# DMD_Output_Interface.net
KiCad netlist of a schematic drawn in Altium Designer
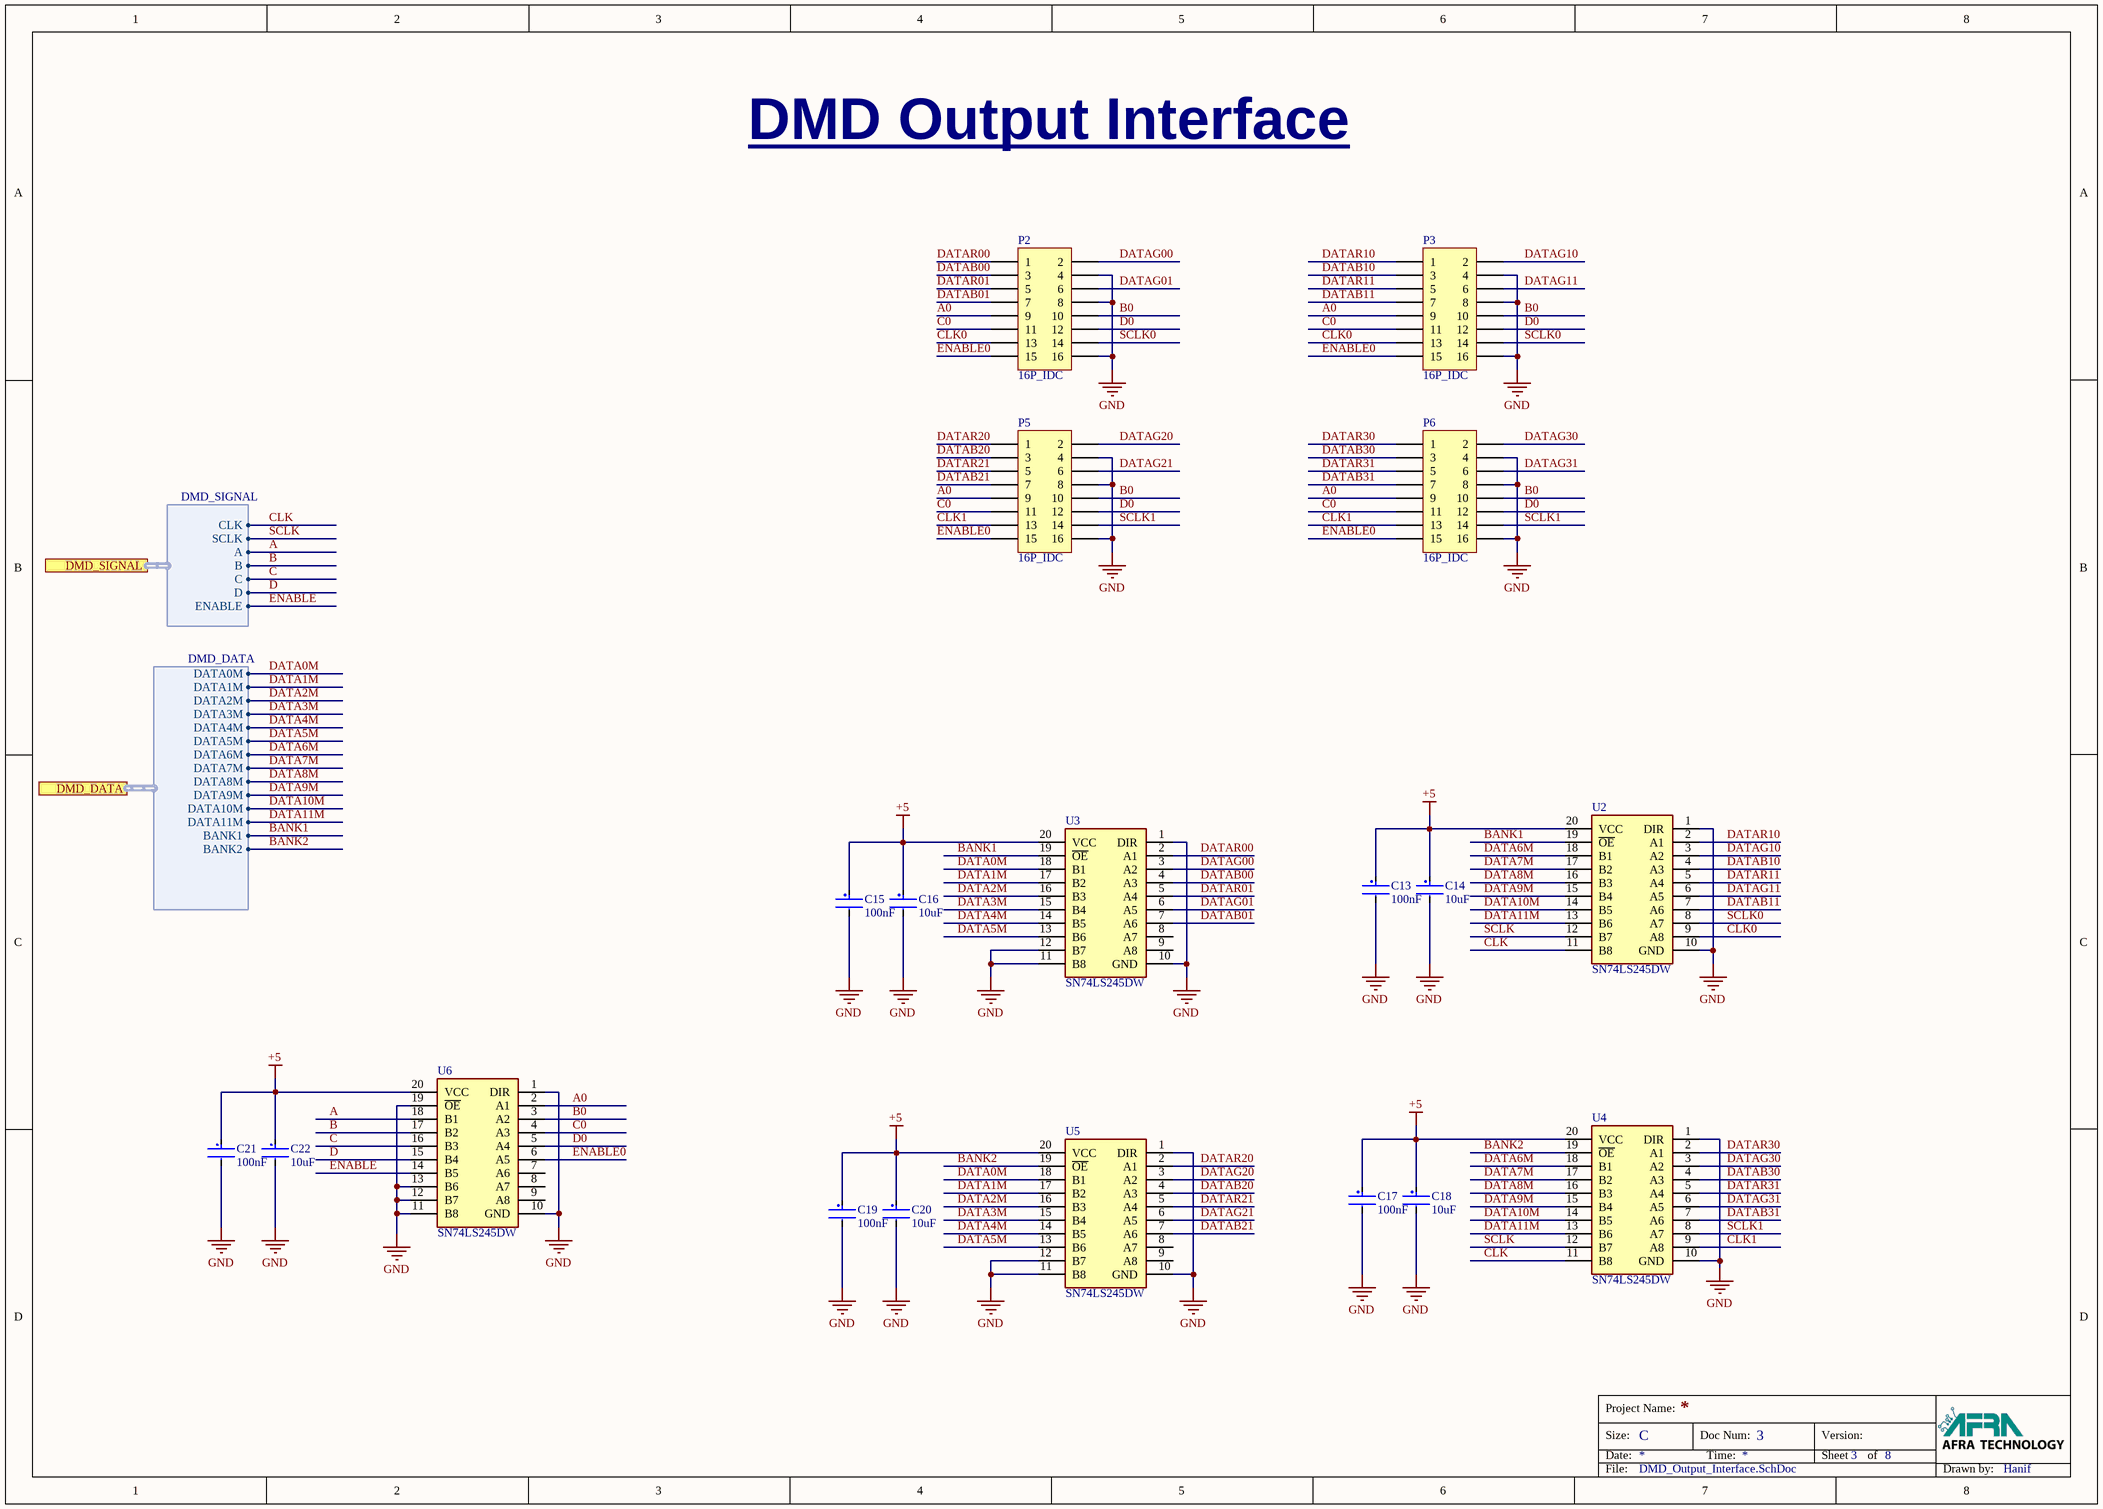
[diagram p0: DMD_Output_Interface.SchDoc]

(export (version "E")
  (design (tool "Eeschema 10.0.6"))
  (components
    (comp (ref "C13")
      (value "100nF")
      (footprint "Samsung_CL31_IPC_A_1206")
      (description "CAP CER 0.1UF 50V X7R 1206, ±10% 50V Ceramic Capacitor X7R 1206 (3216 Metric)")
      (libsource (lib "DMD_Card") (part "CL31B104KBCNFNC"))
    )
    (comp (ref "C14")
      (value "10uF")
      (footprint "Samsung_CL31_IPC_A_1206")
      (description "CAP CER 10UF 6.3V X5R 1206, ±10% 6.3V Ceramic Capacitor X5R 1206 (3216 Metric)")
      (libsource (lib "DMD_Card") (part "CL31A106KQHNNWE"))
    )
    (comp (ref "C15")
      (value "100nF")
      (footprint "Samsung_CL31_IPC_A_1206")
      (description "CAP CER 0.1UF 50V X7R 1206, ±10% 50V Ceramic Capacitor X7R 1206 (3216 Metric)")
      (libsource (lib "DMD_Card") (part "CL31B104KBCNFNC"))
    )
    (comp (ref "C16")
      (value "10uF")
      (footprint "Samsung_CL31_IPC_A_1206")
      (description "CAP CER 10UF 6.3V X5R 1206, ±10% 6.3V Ceramic Capacitor X5R 1206 (3216 Metric)")
      (libsource (lib "DMD_Card") (part "CL31A106KQHNNWE"))
    )
    (comp (ref "C17")
      (value "100nF")
      (footprint "Samsung_CL31_IPC_A_1206")
      (description "CAP CER 0.1UF 50V X7R 1206, ±10% 50V Ceramic Capacitor X7R 1206 (3216 Metric)")
      (libsource (lib "DMD_Card") (part "CL31B104KBCNFNC"))
    )
    (comp (ref "C18")
      (value "10uF")
      (footprint "Samsung_CL31_IPC_A_1206")
      (description "CAP CER 10UF 6.3V X5R 1206, ±10% 6.3V Ceramic Capacitor X5R 1206 (3216 Metric)")
      (libsource (lib "DMD_Card") (part "CL31A106KQHNNWE"))
    )
    (comp (ref "C19")
      (value "100nF")
      (footprint "Samsung_CL31_IPC_A_1206")
      (description "CAP CER 0.1UF 50V X7R 1206, ±10% 50V Ceramic Capacitor X7R 1206 (3216 Metric)")
      (libsource (lib "DMD_Card") (part "CL31B104KBCNFNC"))
    )
    (comp (ref "C20")
      (value "10uF")
      (footprint "Samsung_CL31_IPC_A_1206")
      (description "CAP CER 10UF 6.3V X5R 1206, ±10% 6.3V Ceramic Capacitor X5R 1206 (3216 Metric)")
      (libsource (lib "DMD_Card") (part "CL31A106KQHNNWE"))
    )
    (comp (ref "C21")
      (value "100nF")
      (footprint "Samsung_CL31_IPC_A_1206")
      (description "CAP CER 0.1UF 50V X7R 1206, ±10% 50V Ceramic Capacitor X7R 1206 (3216 Metric)")
      (libsource (lib "DMD_Card") (part "CL31B104KBCNFNC"))
    )
    (comp (ref "C22")
      (value "10uF")
      (footprint "Samsung_CL31_IPC_A_1206")
      (description "CAP CER 10UF 6.3V X5R 1206, ±10% 6.3V Ceramic Capacitor X5R 1206 (3216 Metric)")
      (libsource (lib "DMD_Card") (part "CL31A106KQHNNWE"))
    )
    (comp (ref "P2")
      (value "16P_IDC")
      (footprint "16Pin_IDC_Connector")
      (description "Headers & Wire Housings 16P STRAIGHT")
      (fields
        (field (name "MANUFACTURER") "Adam Equipment")
        (field (name "MANUFACTURER PART NUMBER") "BHR-16-VUA")
      )
      (libsource (lib "DMD_Card") (part "BHR-16-VUA"))
    )
    (comp (ref "P3")
      (value "16P_IDC")
      (footprint "16Pin_IDC_Connector")
      (description "Headers & Wire Housings 16P STRAIGHT")
      (fields
        (field (name "MANUFACTURER") "Adam Equipment")
        (field (name "MANUFACTURER PART NUMBER") "BHR-16-VUA")
      )
      (libsource (lib "DMD_Card") (part "BHR-16-VUA"))
    )
    (comp (ref "P5")
      (value "16P_IDC")
      (footprint "16Pin_IDC_Connector")
      (description "Headers & Wire Housings 16P STRAIGHT")
      (fields
        (field (name "MANUFACTURER") "Adam Equipment")
        (field (name "MANUFACTURER PART NUMBER") "BHR-16-VUA")
      )
      (libsource (lib "DMD_Card") (part "BHR-16-VUA"))
    )
    (comp (ref "P6")
      (value "16P_IDC")
      (footprint "16Pin_IDC_Connector")
      (description "Headers & Wire Housings 16P STRAIGHT")
      (fields
        (field (name "MANUFACTURER") "Adam Equipment")
        (field (name "MANUFACTURER PART NUMBER") "BHR-16-VUA")
      )
      (libsource (lib "DMD_Card") (part "BHR-16-VUA"))
    )
    (comp (ref "U2")
      (value "SN74LS245DW")
      (footprint "SOIC127P1030X265-20N")
      (description "Integrated Circuit")
      (fields (field (name "MOUSER PART NUMBER") "595-SN74LS245DW"))
      (libsource (lib "DMD_Controller_Card") (part "SN74LS245DW"))
    )
    (comp (ref "U3")
      (value "SN74LS245DW")
      (footprint "SOIC127P1030X265-20N")
      (description "Integrated Circuit")
      (fields (field (name "MOUSER PART NUMBER") "595-SN74LS245DW"))
      (libsource (lib "DMD_Controller_Card") (part "SN74LS245DW"))
    )
    (comp (ref "U4")
      (value "SN74LS245DW")
      (footprint "SOIC127P1030X265-20N")
      (description "Integrated Circuit")
      (fields (field (name "MOUSER PART NUMBER") "595-SN74LS245DW"))
      (libsource (lib "DMD_Controller_Card") (part "SN74LS245DW"))
    )
    (comp (ref "U5")
      (value "SN74LS245DW")
      (footprint "SOIC127P1030X265-20N")
      (description "Integrated Circuit")
      (fields (field (name "MOUSER PART NUMBER") "595-SN74LS245DW"))
      (libsource (lib "DMD_Controller_Card") (part "SN74LS245DW"))
    )
    (comp (ref "U6")
      (value "SN74LS245DW")
      (footprint "SOIC127P1030X265-20N")
      (description "Integrated Circuit")
      (fields (field (name "MOUSER PART NUMBER") "595-SN74LS245DW"))
      (libsource (lib "DMD_Controller_Card") (part "SN74LS245DW"))
    )
  )
  (nets
    (net (code "3") (name "+5") (class "Default")
      (node (ref "C13") (pin "1") (pinfunction "1_1") (pintype "passive"))
      (node (ref "C14") (pin "1") (pinfunction "1_1") (pintype "passive"))
      (node (ref "C15") (pin "1") (pinfunction "1_1") (pintype "passive"))
      (node (ref "C16") (pin "1") (pinfunction "1_1") (pintype "passive"))
      (node (ref "C17") (pin "1") (pinfunction "1_1") (pintype "passive"))
      (node (ref "C18") (pin "1") (pinfunction "1_1") (pintype "passive"))
      (node (ref "C19") (pin "1") (pinfunction "1_1") (pintype "passive"))
      (node (ref "C20") (pin "1") (pinfunction "1_1") (pintype "passive"))
      (node (ref "C21") (pin "1") (pinfunction "1_1") (pintype "passive"))
      (node (ref "C22") (pin "1") (pinfunction "1_1") (pintype "passive"))
      (node (ref "U2") (pin "20") (pinfunction "VCC_20") (pintype "passive"))
      (node (ref "U3") (pin "20") (pinfunction "VCC_20") (pintype "passive"))
      (node (ref "U4") (pin "20") (pinfunction "VCC_20") (pintype "passive"))
      (node (ref "U5") (pin "20") (pinfunction "VCC_20") (pintype "passive"))
      (node (ref "U6") (pin "20") (pinfunction "VCC_20") (pintype "passive"))
    )
    (net (code "4") (name "/A") (class "Default")
      (node (ref "U6") (pin "18") (pinfunction "B1_18") (pintype "passive"))
    )
    (net (code "5") (name "/A0") (class "Default")
      (node (ref "P2") (pin "9") (pinfunction "9_9") (pintype "passive"))
      (node (ref "P3") (pin "9") (pinfunction "9_9") (pintype "passive"))
      (node (ref "P5") (pin "9") (pinfunction "9_9") (pintype "passive"))
      (node (ref "P6") (pin "9") (pinfunction "9_9") (pintype "passive"))
      (node (ref "U6") (pin "2") (pinfunction "A1_2") (pintype "passive"))
    )
    (net (code "6") (name "/B") (class "Default")
      (node (ref "U6") (pin "17") (pinfunction "B2_17") (pintype "passive"))
    )
    (net (code "7") (name "/B0") (class "Default")
      (node (ref "P2") (pin "10") (pinfunction "10_10") (pintype "passive"))
      (node (ref "P3") (pin "10") (pinfunction "10_10") (pintype "passive"))
      (node (ref "P5") (pin "10") (pinfunction "10_10") (pintype "passive"))
      (node (ref "P6") (pin "10") (pinfunction "10_10") (pintype "passive"))
      (node (ref "U6") (pin "3") (pinfunction "A2_3") (pintype "passive"))
    )
    (net (code "8") (name "/BANK1") (class "Default")
      (node (ref "U2") (pin "19") (pinfunction "~{OE}_19") (pintype "passive"))
      (node (ref "U3") (pin "19") (pinfunction "~{OE}_19") (pintype "passive"))
    )
    (net (code "9") (name "/BANK2") (class "Default")
      (node (ref "U4") (pin "19") (pinfunction "~{OE}_19") (pintype "passive"))
      (node (ref "U5") (pin "19") (pinfunction "~{OE}_19") (pintype "passive"))
    )
    (net (code "10") (name "/C") (class "Default")
      (node (ref "U6") (pin "16") (pinfunction "B3_16") (pintype "passive"))
    )
    (net (code "11") (name "/C0") (class "Default")
      (node (ref "P2") (pin "11") (pinfunction "11_11") (pintype "passive"))
      (node (ref "P3") (pin "11") (pinfunction "11_11") (pintype "passive"))
      (node (ref "P5") (pin "11") (pinfunction "11_11") (pintype "passive"))
      (node (ref "P6") (pin "11") (pinfunction "11_11") (pintype "passive"))
      (node (ref "U6") (pin "4") (pinfunction "A3_4") (pintype "passive"))
    )
    (net (code "12") (name "/CLK") (class "Default")
      (node (ref "U2") (pin "11") (pinfunction "B8_11") (pintype "passive"))
      (node (ref "U4") (pin "11") (pinfunction "B8_11") (pintype "passive"))
    )
    (net (code "13") (name "/CLK0") (class "Default")
      (node (ref "P2") (pin "13") (pinfunction "13_13") (pintype "passive"))
      (node (ref "P3") (pin "13") (pinfunction "13_13") (pintype "passive"))
      (node (ref "U2") (pin "9") (pinfunction "A8_9") (pintype "passive"))
    )
    (net (code "14") (name "/CLK1") (class "Default")
      (node (ref "P5") (pin "13") (pinfunction "13_13") (pintype "passive"))
      (node (ref "P6") (pin "13") (pinfunction "13_13") (pintype "passive"))
      (node (ref "U4") (pin "9") (pinfunction "A8_9") (pintype "passive"))
    )
    (net (code "15") (name "/D") (class "Default")
      (node (ref "U6") (pin "15") (pinfunction "B4_15") (pintype "passive"))
    )
    (net (code "16") (name "/D0") (class "Default")
      (node (ref "P2") (pin "12") (pinfunction "12_12") (pintype "passive"))
      (node (ref "P3") (pin "12") (pinfunction "12_12") (pintype "passive"))
      (node (ref "P5") (pin "12") (pinfunction "12_12") (pintype "passive"))
      (node (ref "P6") (pin "12") (pinfunction "12_12") (pintype "passive"))
      (node (ref "U6") (pin "5") (pinfunction "A4_5") (pintype "passive"))
    )
    (net (code "17") (name "/DATA0M") (class "Default")
      (node (ref "U3") (pin "18") (pinfunction "B1_18") (pintype "passive"))
      (node (ref "U5") (pin "18") (pinfunction "B1_18") (pintype "passive"))
    )
    (net (code "18") (name "/DATA1M") (class "Default")
      (node (ref "U3") (pin "17") (pinfunction "B2_17") (pintype "passive"))
      (node (ref "U5") (pin "17") (pinfunction "B2_17") (pintype "passive"))
    )
    (net (code "19") (name "/DATA2M") (class "Default")
      (node (ref "U3") (pin "16") (pinfunction "B3_16") (pintype "passive"))
      (node (ref "U5") (pin "16") (pinfunction "B3_16") (pintype "passive"))
    )
    (net (code "20") (name "/DATA3M") (class "Default")
      (node (ref "U3") (pin "15") (pinfunction "B4_15") (pintype "passive"))
      (node (ref "U5") (pin "15") (pinfunction "B4_15") (pintype "passive"))
    )
    (net (code "21") (name "/DATA4M") (class "Default")
      (node (ref "U3") (pin "14") (pinfunction "B5_14") (pintype "passive"))
      (node (ref "U5") (pin "14") (pinfunction "B5_14") (pintype "passive"))
    )
    (net (code "22") (name "/DATA5M") (class "Default")
      (node (ref "U3") (pin "13") (pinfunction "B6_13") (pintype "passive"))
      (node (ref "U5") (pin "13") (pinfunction "B6_13") (pintype "passive"))
    )
    (net (code "23") (name "/DATA6M") (class "Default")
      (node (ref "U2") (pin "18") (pinfunction "B1_18") (pintype "passive"))
      (node (ref "U4") (pin "18") (pinfunction "B1_18") (pintype "passive"))
    )
    (net (code "24") (name "/DATA7M") (class "Default")
      (node (ref "U2") (pin "17") (pinfunction "B2_17") (pintype "passive"))
      (node (ref "U4") (pin "17") (pinfunction "B2_17") (pintype "passive"))
    )
    (net (code "25") (name "/DATA8M") (class "Default")
      (node (ref "U2") (pin "16") (pinfunction "B3_16") (pintype "passive"))
      (node (ref "U4") (pin "16") (pinfunction "B3_16") (pintype "passive"))
    )
    (net (code "26") (name "/DATA9M") (class "Default")
      (node (ref "U2") (pin "15") (pinfunction "B4_15") (pintype "passive"))
      (node (ref "U4") (pin "15") (pinfunction "B4_15") (pintype "passive"))
    )
    (net (code "27") (name "/DATA10M") (class "Default")
      (node (ref "U2") (pin "14") (pinfunction "B5_14") (pintype "passive"))
      (node (ref "U4") (pin "14") (pinfunction "B5_14") (pintype "passive"))
    )
    (net (code "28") (name "/DATA11M") (class "Default")
      (node (ref "U2") (pin "13") (pinfunction "B6_13") (pintype "passive"))
      (node (ref "U4") (pin "13") (pinfunction "B6_13") (pintype "passive"))
    )
    (net (code "29") (name "/DATAB00") (class "Default")
      (node (ref "P2") (pin "3") (pinfunction "3_3") (pintype "passive"))
      (node (ref "U3") (pin "4") (pinfunction "A3_4") (pintype "passive"))
    )
    (net (code "30") (name "/DATAB01") (class "Default")
      (node (ref "P2") (pin "7") (pinfunction "7_7") (pintype "passive"))
      (node (ref "U3") (pin "7") (pinfunction "A6_7") (pintype "passive"))
    )
    (net (code "31") (name "/DATAB10") (class "Default")
      (node (ref "P3") (pin "3") (pinfunction "3_3") (pintype "passive"))
      (node (ref "U2") (pin "4") (pinfunction "A3_4") (pintype "passive"))
    )
    (net (code "32") (name "/DATAB11") (class "Default")
      (node (ref "P3") (pin "7") (pinfunction "7_7") (pintype "passive"))
      (node (ref "U2") (pin "7") (pinfunction "A6_7") (pintype "passive"))
    )
    (net (code "33") (name "/DATAB20") (class "Default")
      (node (ref "P5") (pin "3") (pinfunction "3_3") (pintype "passive"))
      (node (ref "U5") (pin "4") (pinfunction "A3_4") (pintype "passive"))
    )
    (net (code "34") (name "/DATAB21") (class "Default")
      (node (ref "P5") (pin "7") (pinfunction "7_7") (pintype "passive"))
      (node (ref "U5") (pin "7") (pinfunction "A6_7") (pintype "passive"))
    )
    (net (code "35") (name "/DATAB30") (class "Default")
      (node (ref "P6") (pin "3") (pinfunction "3_3") (pintype "passive"))
      (node (ref "U4") (pin "4") (pinfunction "A3_4") (pintype "passive"))
    )
    (net (code "36") (name "/DATAB31") (class "Default")
      (node (ref "P6") (pin "7") (pinfunction "7_7") (pintype "passive"))
      (node (ref "U4") (pin "7") (pinfunction "A6_7") (pintype "passive"))
    )
    (net (code "37") (name "/DATAG00") (class "Default")
      (node (ref "P2") (pin "2") (pinfunction "2_2") (pintype "passive"))
      (node (ref "U3") (pin "3") (pinfunction "A2_3") (pintype "passive"))
    )
    (net (code "38") (name "/DATAG01") (class "Default")
      (node (ref "P2") (pin "6") (pinfunction "6_6") (pintype "passive"))
      (node (ref "U3") (pin "6") (pinfunction "A5_6") (pintype "passive"))
    )
    (net (code "39") (name "/DATAG10") (class "Default")
      (node (ref "P3") (pin "2") (pinfunction "2_2") (pintype "passive"))
      (node (ref "U2") (pin "3") (pinfunction "A2_3") (pintype "passive"))
    )
    (net (code "40") (name "/DATAG11") (class "Default")
      (node (ref "P3") (pin "6") (pinfunction "6_6") (pintype "passive"))
      (node (ref "U2") (pin "6") (pinfunction "A5_6") (pintype "passive"))
    )
    (net (code "41") (name "/DATAG20") (class "Default")
      (node (ref "P5") (pin "2") (pinfunction "2_2") (pintype "passive"))
      (node (ref "U5") (pin "3") (pinfunction "A2_3") (pintype "passive"))
    )
    (net (code "42") (name "/DATAG21") (class "Default")
      (node (ref "P5") (pin "6") (pinfunction "6_6") (pintype "passive"))
      (node (ref "U5") (pin "6") (pinfunction "A5_6") (pintype "passive"))
    )
    (net (code "43") (name "/DATAG30") (class "Default")
      (node (ref "P6") (pin "2") (pinfunction "2_2") (pintype "passive"))
      (node (ref "U4") (pin "3") (pinfunction "A2_3") (pintype "passive"))
    )
    (net (code "44") (name "/DATAG31") (class "Default")
      (node (ref "P6") (pin "6") (pinfunction "6_6") (pintype "passive"))
      (node (ref "U4") (pin "6") (pinfunction "A5_6") (pintype "passive"))
    )
    (net (code "45") (name "/DATAR00") (class "Default")
      (node (ref "P2") (pin "1") (pinfunction "1_1") (pintype "passive"))
      (node (ref "U3") (pin "2") (pinfunction "A1_2") (pintype "passive"))
    )
    (net (code "46") (name "/DATAR01") (class "Default")
      (node (ref "P2") (pin "5") (pinfunction "5_5") (pintype "passive"))
      (node (ref "U3") (pin "5") (pinfunction "A4_5") (pintype "passive"))
    )
    (net (code "47") (name "/DATAR10") (class "Default")
      (node (ref "P3") (pin "1") (pinfunction "1_1") (pintype "passive"))
      (node (ref "U2") (pin "2") (pinfunction "A1_2") (pintype "passive"))
    )
    (net (code "48") (name "/DATAR11") (class "Default")
      (node (ref "P3") (pin "5") (pinfunction "5_5") (pintype "passive"))
      (node (ref "U2") (pin "5") (pinfunction "A4_5") (pintype "passive"))
    )
    (net (code "49") (name "/DATAR20") (class "Default")
      (node (ref "P5") (pin "1") (pinfunction "1_1") (pintype "passive"))
      (node (ref "U5") (pin "2") (pinfunction "A1_2") (pintype "passive"))
    )
    (net (code "50") (name "/DATAR21") (class "Default")
      (node (ref "P5") (pin "5") (pinfunction "5_5") (pintype "passive"))
      (node (ref "U5") (pin "5") (pinfunction "A4_5") (pintype "passive"))
    )
    (net (code "51") (name "/DATAR30") (class "Default")
      (node (ref "P6") (pin "1") (pinfunction "1_1") (pintype "passive"))
      (node (ref "U4") (pin "2") (pinfunction "A1_2") (pintype "passive"))
    )
    (net (code "52") (name "/DATAR31") (class "Default")
      (node (ref "P6") (pin "5") (pinfunction "5_5") (pintype "passive"))
      (node (ref "U4") (pin "5") (pinfunction "A4_5") (pintype "passive"))
    )
    (net (code "53") (name "/ENABLE") (class "Default")
      (node (ref "U6") (pin "14") (pinfunction "B5_14") (pintype "passive"))
    )
    (net (code "54") (name "/ENABLE0") (class "Default")
      (node (ref "P2") (pin "15") (pinfunction "15_15") (pintype "passive"))
      (node (ref "P3") (pin "15") (pinfunction "15_15") (pintype "passive"))
      (node (ref "P5") (pin "15") (pinfunction "15_15") (pintype "passive"))
      (node (ref "P6") (pin "15") (pinfunction "15_15") (pintype "passive"))
      (node (ref "U6") (pin "6") (pinfunction "A5_6") (pintype "passive"))
    )
    (net (code "55") (name "/SCLK") (class "Default")
      (node (ref "U2") (pin "12") (pinfunction "B7_12") (pintype "passive"))
      (node (ref "U4") (pin "12") (pinfunction "B7_12") (pintype "passive"))
    )
    (net (code "56") (name "/SCLK0") (class "Default")
      (node (ref "P2") (pin "14") (pinfunction "14_14") (pintype "passive"))
      (node (ref "P3") (pin "14") (pinfunction "14_14") (pintype "passive"))
      (node (ref "U2") (pin "8") (pinfunction "A7_8") (pintype "passive"))
    )
    (net (code "57") (name "/SCLK1") (class "Default")
      (node (ref "P5") (pin "14") (pinfunction "14_14") (pintype "passive"))
      (node (ref "P6") (pin "14") (pinfunction "14_14") (pintype "passive"))
      (node (ref "U4") (pin "8") (pinfunction "A7_8") (pintype "passive"))
    )
    (net (code "60") (name "GND") (class "Default")
      (node (ref "C13") (pin "2") (pinfunction "2_2") (pintype "passive"))
      (node (ref "C14") (pin "2") (pinfunction "2_2") (pintype "passive"))
      (node (ref "C15") (pin "2") (pinfunction "2_2") (pintype "passive"))
      (node (ref "C16") (pin "2") (pinfunction "2_2") (pintype "passive"))
      (node (ref "C17") (pin "2") (pinfunction "2_2") (pintype "passive"))
      (node (ref "C18") (pin "2") (pinfunction "2_2") (pintype "passive"))
      (node (ref "C19") (pin "2") (pinfunction "2_2") (pintype "passive"))
      (node (ref "C20") (pin "2") (pinfunction "2_2") (pintype "passive"))
      (node (ref "C21") (pin "2") (pinfunction "2_2") (pintype "passive"))
      (node (ref "C22") (pin "2") (pinfunction "2_2") (pintype "passive"))
      (node (ref "P2") (pin "16") (pinfunction "16_16") (pintype "passive"))
      (node (ref "P2") (pin "4") (pinfunction "4_4") (pintype "passive"))
      (node (ref "P2") (pin "8") (pinfunction "8_8") (pintype "passive"))
      (node (ref "P3") (pin "16") (pinfunction "16_16") (pintype "passive"))
      (node (ref "P3") (pin "4") (pinfunction "4_4") (pintype "passive"))
      (node (ref "P3") (pin "8") (pinfunction "8_8") (pintype "passive"))
      (node (ref "P5") (pin "16") (pinfunction "16_16") (pintype "passive"))
      (node (ref "P5") (pin "4") (pinfunction "4_4") (pintype "passive"))
      (node (ref "P5") (pin "8") (pinfunction "8_8") (pintype "passive"))
      (node (ref "P6") (pin "16") (pinfunction "16_16") (pintype "passive"))
      (node (ref "P6") (pin "4") (pinfunction "4_4") (pintype "passive"))
      (node (ref "P6") (pin "8") (pinfunction "8_8") (pintype "passive"))
      (node (ref "U2") (pin "1") (pinfunction "DIR_1") (pintype "passive"))
      (node (ref "U2") (pin "10") (pinfunction "GND_10") (pintype "passive"))
      (node (ref "U3") (pin "1") (pinfunction "DIR_1") (pintype "passive"))
      (node (ref "U3") (pin "10") (pinfunction "GND_10") (pintype "passive"))
      (node (ref "U3") (pin "11") (pinfunction "B8_11") (pintype "passive"))
      (node (ref "U3") (pin "12") (pinfunction "B7_12") (pintype "passive"))
      (node (ref "U4") (pin "1") (pinfunction "DIR_1") (pintype "passive"))
      (node (ref "U4") (pin "10") (pinfunction "GND_10") (pintype "passive"))
      (node (ref "U5") (pin "1") (pinfunction "DIR_1") (pintype "passive"))
      (node (ref "U5") (pin "10") (pinfunction "GND_10") (pintype "passive"))
      (node (ref "U5") (pin "11") (pinfunction "B8_11") (pintype "passive"))
      (node (ref "U5") (pin "12") (pinfunction "B7_12") (pintype "passive"))
      (node (ref "U6") (pin "1") (pinfunction "DIR_1") (pintype "passive"))
      (node (ref "U6") (pin "10") (pinfunction "GND_10") (pintype "passive"))
      (node (ref "U6") (pin "11") (pinfunction "B8_11") (pintype "passive"))
      (node (ref "U6") (pin "12") (pinfunction "B7_12") (pintype "passive"))
      (node (ref "U6") (pin "13") (pinfunction "B6_13") (pintype "passive"))
      (node (ref "U6") (pin "19") (pinfunction "~{OE}_19") (pintype "passive"))
    )
    (net (code "61") (name "unconnected-(U3-A7-Pad8)") (class "Default")
      (node (ref "U3") (pin "8") (pinfunction "A7_8") (pintype "passive"))
    )
    (net (code "62") (name "unconnected-(U3-A8-Pad9)") (class "Default")
      (node (ref "U3") (pin "9") (pinfunction "A8_9") (pintype "passive"))
    )
    (net (code "63") (name "unconnected-(U5-A7-Pad8)") (class "Default")
      (node (ref "U5") (pin "8") (pinfunction "A7_8") (pintype "passive"))
    )
    (net (code "64") (name "unconnected-(U5-A8-Pad9)") (class "Default")
      (node (ref "U5") (pin "9") (pinfunction "A8_9") (pintype "passive"))
    )
    (net (code "65") (name "unconnected-(U6-A6-Pad7)") (class "Default")
      (node (ref "U6") (pin "7") (pinfunction "A6_7") (pintype "passive"))
    )
    (net (code "66") (name "unconnected-(U6-A7-Pad8)") (class "Default")
      (node (ref "U6") (pin "8") (pinfunction "A7_8") (pintype "passive"))
    )
    (net (code "67") (name "unconnected-(U6-A8-Pad9)") (class "Default")
      (node (ref "U6") (pin "9") (pinfunction "A8_9") (pintype "passive"))
    )
  )
)
